# CPU_DIN_mainboard_power.net
KiCad netlist of a schematic drawn in Altium Designer
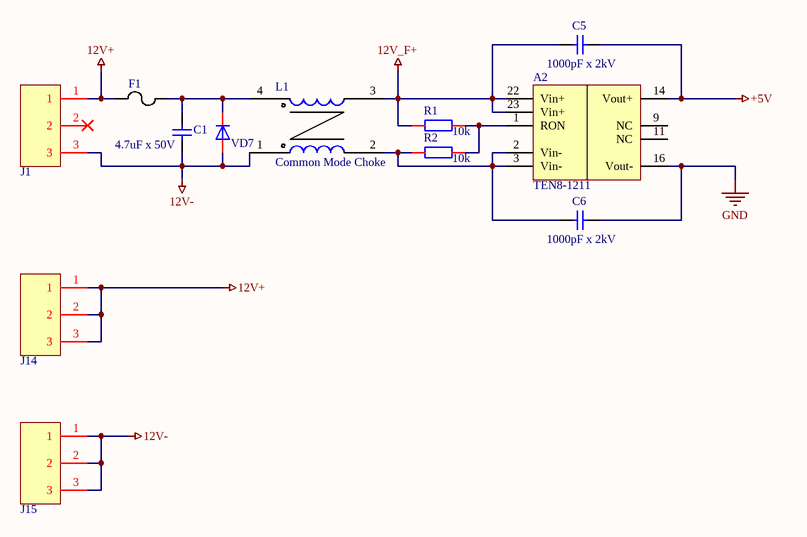
[diagram p0: CPU_DIN_mainboard_power.SchDoc]

(export (version "E")
  (design (tool "Eeschema 10.0.6"))
  (components
    (comp (ref "A2")
      (value "TEN8-1211")
      (footprint "dcdc_ten8-1211")
      (description "Traco Isolated DC/DC")
      (libsource (lib "Lib_001") (part "TEN8-1211"))
    )
    (comp (ref "C1")
      (value "4.7uF x 50V")
      (footprint "C1206")
      (fields (field (name "PARTNUM") "GRM31CR71H475KA12L"))
      (libsource (lib "Lib_001") (part "CAP_SMD"))
    )
    (comp (ref "C5") (value "1000pF x 2kV") (footprint "c1206") (libsource (lib "Lib_001") (part "CAP_SMD")))
    (comp (ref "C6") (value "1000pF x 2kV") (footprint "c1206") (libsource (lib "Lib_001") (part "CAP_SMD")))
    (comp (ref "F1")
      (value "FUSE")
      (footprint "MF-SM100")
      (fields (field (name "PARTNUM") "MF-SM100-2"))
      (libsource (lib "Lib_001") (part "FUSE"))
    )
    (comp (ref "J1")
      (value "Terminal block TB-3")
      (footprint "TB-3_ser370")
      (libsource (lib "Lib_001") (part "TB-3"))
    )
    (comp (ref "J14")
      (value "Terminal block TB-3")
      (footprint "TB-3_ser370")
      (libsource (lib "Lib_001") (part "TB-3"))
    )
    (comp (ref "J15")
      (value "Terminal block TB-3")
      (footprint "TB-3_ser370")
      (libsource (lib "Lib_001") (part "TB-3"))
    )
    (comp (ref "L1")
      (value "Common Mode Choke")
      (footprint "TCK-050")
      (fields (field (name "PARTNUM") "TCK-050"))
      (libsource (lib "Lib_001") (part "L_CHOKE"))
    )
    (comp (ref "R1") (value "10k") (footprint "R0805") (libsource (lib "Lib_001") (part "RES_SMD")))
    (comp (ref "R2") (value "10k") (footprint "R0805") (libsource (lib "Lib_001") (part "RES_SMD")))
    (comp (ref "VD7")
      (value "15MQ040N")
      (footprint "SMA DIOD")
      (fields (field (name "PARTNUM") "VS-15MQ040NTRPBF"))
      (libsource (lib "Lib_001") (part "DIOD"))
    )
  )
  (nets
    (net (code "1") (name "+5V") (class "Default")
      (node (ref "A2") (pin "14") (pinfunction "Vout+_14") (pintype "passive"))
      (node (ref "C5") (pin "2") (pinfunction "2_2") (pintype "passive"))
    )
    (net (code "2") (name "12V+") (class "Default")
      (node (ref "F1") (pin "1") (pinfunction "1_1") (pintype "passive"))
      (node (ref "J1") (pin "1") (pinfunction "1_1") (pintype "passive"))
      (node (ref "J14") (pin "1") (pinfunction "1_1") (pintype "passive"))
      (node (ref "J14") (pin "2") (pinfunction "2_2") (pintype "passive"))
      (node (ref "J14") (pin "3") (pinfunction "3_3") (pintype "passive"))
    )
    (net (code "3") (name "12V-") (class "Default")
      (node (ref "C1") (pin "2") (pinfunction "2_2") (pintype "passive"))
      (node (ref "J1") (pin "3") (pinfunction "3_3") (pintype "passive"))
      (node (ref "J15") (pin "1") (pinfunction "1_1") (pintype "passive"))
      (node (ref "J15") (pin "2") (pinfunction "2_2") (pintype "passive"))
      (node (ref "J15") (pin "3") (pinfunction "3_3") (pintype "passive"))
      (node (ref "L1") (pin "1") (pinfunction "1_1") (pintype "passive"))
      (node (ref "VD7") (pin "A") (pinfunction "A_A") (pintype "passive"))
    )
    (net (code "4") (name "12V_F+") (class "Default")
      (node (ref "A2") (pin "22") (pinfunction "Vin+_22") (pintype "passive"))
      (node (ref "A2") (pin "23") (pinfunction "Vin+_23") (pintype "passive"))
      (node (ref "C5") (pin "1") (pinfunction "1_1") (pintype "passive"))
      (node (ref "L1") (pin "3") (pinfunction "3_3") (pintype "passive"))
      (node (ref "R1") (pin "2") (pinfunction "2_2") (pintype "passive"))
    )
    (net (code "5") (name "GND") (class "Default")
      (node (ref "A2") (pin "16") (pinfunction "Vout-_16") (pintype "passive"))
      (node (ref "C6") (pin "2") (pinfunction "2_2") (pintype "passive"))
    )
    (net (code "6") (name "Net-(A2-RON)") (class "Default")
      (node (ref "A2") (pin "1") (pinfunction "RON_1") (pintype "passive"))
      (node (ref "R1") (pin "1") (pinfunction "1_1") (pintype "passive"))
      (node (ref "R2") (pin "1") (pinfunction "1_1") (pintype "passive"))
    )
    (net (code "7") (name "Net-(A2-Vin--Pad2)") (class "Default")
      (node (ref "A2") (pin "2") (pinfunction "Vin-_2") (pintype "passive"))
      (node (ref "A2") (pin "3") (pinfunction "Vin-_3") (pintype "passive"))
      (node (ref "C6") (pin "1") (pinfunction "1_1") (pintype "passive"))
      (node (ref "L1") (pin "2") (pinfunction "2_2") (pintype "passive"))
      (node (ref "R2") (pin "2") (pinfunction "2_2") (pintype "passive"))
    )
    (net (code "8") (name "Net-(C1-Pad1)") (class "Default")
      (node (ref "C1") (pin "1") (pinfunction "1_1") (pintype "passive"))
      (node (ref "F1") (pin "2") (pinfunction "2_2") (pintype "passive"))
      (node (ref "L1") (pin "4") (pinfunction "4_4") (pintype "passive"))
      (node (ref "VD7") (pin "K") (pinfunction "K_K") (pintype "passive"))
    )
    (net (code "9") (name "unconnected-(A2-NC-Pad9)") (class "Default")
      (node (ref "A2") (pin "9") (pinfunction "NC_9") (pintype "passive"))
    )
    (net (code "10") (name "unconnected-(A2-NC-Pad11)") (class "Default")
      (node (ref "A2") (pin "11") (pinfunction "NC_11") (pintype "passive"))
    )
    (net (code "11") (name "unconnected-(J1-Pad2)") (class "Default")
      (node (ref "J1") (pin "2") (pinfunction "2_2") (pintype "passive+no_connect"))
    )
  )
)
